# SCH_uCompute_remote_2026-03-16.net
KiCad netlist of a schematic drawn in EasyEDA
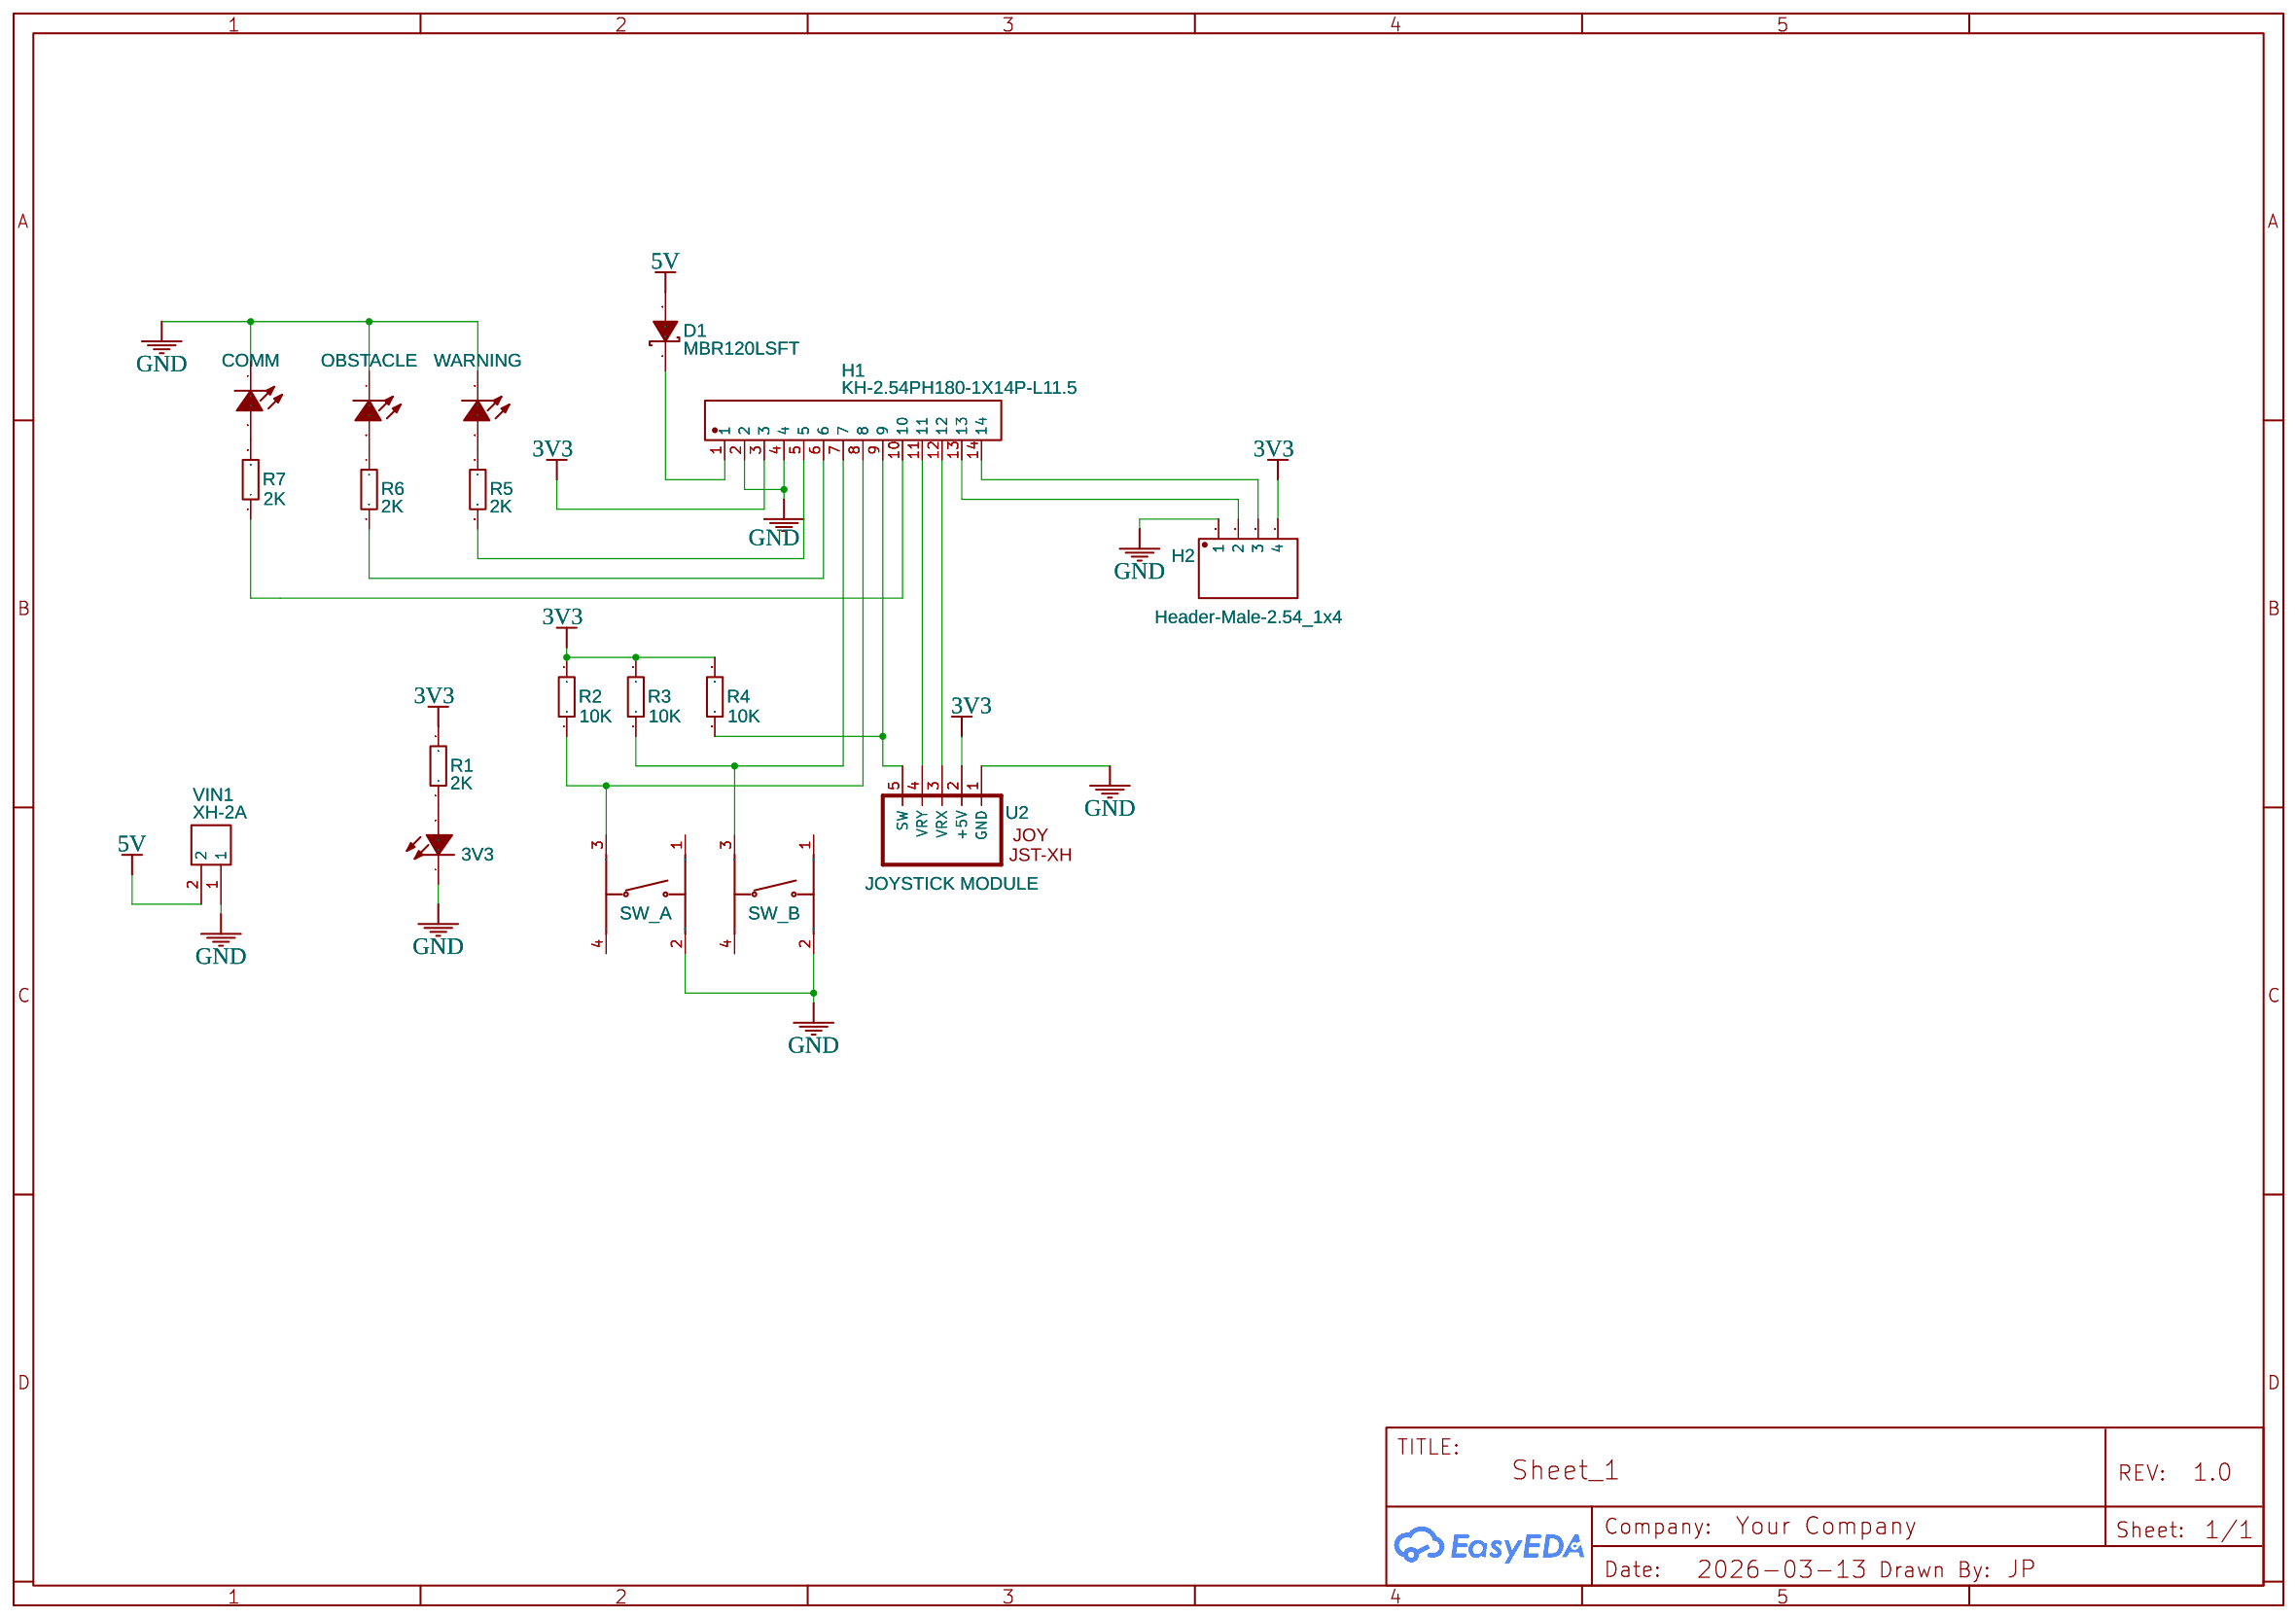
[diagram p0: schematic sheet]

(export (version "E")
  (design (tool "Eeschema 10.0.6"))
  (components
    (comp (ref "3V3")
      (value "XL-1206QPC")
      (fields (field (name "Manufacturer") "LCSC"))
      (libsource (lib "") (part "XL-1206QPC_1"))
    )
    (comp (ref "COMM")
      (value "XL-1206QPC")
      (fields (field (name "Manufacturer") "LCSC"))
      (libsource (lib "") (part "XL-1206QPC"))
    )
    (comp (ref "D1")
      (value "MBR120LSFT")
      (fields
        (field (name "Manufacturer Part") "SS110A")
        (field (name "Manufacturer") "Yangzhou Yangjie Elec Tech")
      )
      (libsource (lib "") (part "SS110A"))
    )
    (comp (ref "H1")
      (value "KH-2.54PH180-1X14P-L11.5")
      (fields (field (name "Manufacturer") "kinghelm(金航标)"))
      (libsource (lib "") (part "KH-2.54PH180-1X14P-L11.5"))
    )
    (comp (ref "H2")
      (value "Header-Male-2.54_1x4")
      (fields (field (name "Manufacturer Part") "B-2100S04P-A110") (field (name "Manufacturer") "Ckmtw(灿科盟)"))
      (libsource (lib "") (part "Header-Male-2.54_1x4"))
    )
    (comp (ref "OBSTACLE")
      (value "XL-1206QPC")
      (fields (field (name "Manufacturer") "LCSC"))
      (libsource (lib "") (part "XL-1206QPC_3"))
    )
    (comp (ref "R1")
      (value "2K")
      (fields (field (name "Manufacturer Part") "RC0805DR-071KL") (field (name "Manufacturer") "YAGEO(国巨)"))
      (libsource (lib "") (part "RC0805DR-071KL"))
    )
    (comp (ref "R2")
      (value "10K")
      (fields (field (name "Manufacturer Part") "RC0805DR-071KL") (field (name "Manufacturer") "YAGEO(国巨)"))
      (libsource (lib "") (part "RC0805DR-071KL"))
    )
    (comp (ref "R3")
      (value "10K")
      (fields (field (name "Manufacturer Part") "RC0805DR-071KL") (field (name "Manufacturer") "YAGEO(国巨)"))
      (libsource (lib "") (part "RC0805DR-071KL"))
    )
    (comp (ref "R4")
      (value "10K")
      (fields (field (name "Manufacturer Part") "RC0805DR-071KL") (field (name "Manufacturer") "YAGEO(国巨)"))
      (libsource (lib "") (part "RC0805DR-071KL"))
    )
    (comp (ref "R5")
      (value "2K")
      (fields (field (name "Manufacturer Part") "RC0805DR-071KL") (field (name "Manufacturer") "YAGEO(国巨)"))
      (libsource (lib "") (part "RC0805DR-071KL_1"))
    )
    (comp (ref "R6")
      (value "2K")
      (fields (field (name "Manufacturer Part") "RC0805DR-071KL") (field (name "Manufacturer") "YAGEO(国巨)"))
      (libsource (lib "") (part "RC0805DR-071KL_1"))
    )
    (comp (ref "R7")
      (value "2K")
      (fields (field (name "Manufacturer Part") "RC0805DR-071KL") (field (name "Manufacturer") "YAGEO(国巨)"))
      (libsource (lib "") (part "RC0805DR-071KL"))
    )
    (comp (ref "SW_A")
      (value "12X12X7.3")
      (fields (field (name "Manufacturer Part") "12x12x7.3 黄头") (field (name "Manufacturer") "BOOMELE(博穆精密)"))
      (libsource (lib "") (part "12X12X7.3"))
    )
    (comp (ref "SW_B")
      (value "12X12X7.3")
      (fields (field (name "Manufacturer Part") "12x12x7.3 黄头") (field (name "Manufacturer") "BOOMELE(博穆精密)"))
      (libsource (lib "") (part "12X12X7.3_1"))
    )
    (comp (ref "U2") (value "JOYSTICK MODULE") (libsource (lib "") (part "JOYSTICK MODULE")))
    (comp (ref "VIN1")
      (value "XH-2A")
      (fields (field (name "Manufacturer") "BOOMELE(博穆精密)"))
      (libsource (lib "") (part "XH-2A"))
    )
    (comp (ref "WARNING")
      (value "XL-1206QPC")
      (fields (field (name "Manufacturer") "LCSC"))
      (libsource (lib "") (part "XL-1206QPC_2"))
    )
  )
  (nets
    (net (code "1") (name "3V3") (class "Default")
      (node (ref "H1") (pin "3") (pinfunction "3_3") (pintype "unspecified"))
      (node (ref "H2") (pin "4") (pinfunction "4_4") (pintype "unspecified"))
      (node (ref "R1") (pin "2") (pinfunction "2_2") (pintype "unspecified"))
      (node (ref "R2") (pin "2") (pinfunction "2_2") (pintype "unspecified"))
      (node (ref "R3") (pin "2") (pinfunction "2_2") (pintype "unspecified"))
      (node (ref "R4") (pin "2") (pinfunction "2_2") (pintype "unspecified"))
      (node (ref "U2") (pin "2") (pinfunction "+5V_2") (pintype "unspecified"))
    )
    (net (code "2") (name "5V") (class "Default")
      (node (ref "D1") (pin "2") (pinfunction "A_2") (pintype "unspecified"))
      (node (ref "VIN1") (pin "2") (pinfunction "2_2") (pintype "unspecified"))
    )
    (net (code "3") (name "GND") (class "Default")
      (node (ref "3V3") (pin "1") (pinfunction "K_1") (pintype "unspecified"))
      (node (ref "COMM") (pin "1") (pinfunction "K_1") (pintype "unspecified"))
      (node (ref "H1") (pin "2") (pinfunction "2_2") (pintype "unspecified"))
      (node (ref "H1") (pin "4") (pinfunction "4_4") (pintype "unspecified"))
      (node (ref "H2") (pin "1") (pinfunction "1_1") (pintype "unspecified"))
      (node (ref "OBSTACLE") (pin "1") (pinfunction "K_1") (pintype "unspecified"))
      (node (ref "SW_A") (pin "2") (pinfunction "2_2") (pintype "unspecified"))
      (node (ref "SW_B") (pin "2") (pinfunction "2_2") (pintype "unspecified"))
      (node (ref "U2") (pin "1") (pinfunction "GND_1") (pintype "unspecified"))
      (node (ref "VIN1") (pin "1") (pinfunction "1_1") (pintype "unspecified"))
      (node (ref "WARNING") (pin "1") (pinfunction "K_1") (pintype "unspecified"))
    )
    (net (code "4") (name "Net-(3V3-A)") (class "Default")
      (node (ref "3V3") (pin "2") (pinfunction "A_2") (pintype "unspecified"))
      (node (ref "R1") (pin "1") (pinfunction "1_1") (pintype "unspecified"))
    )
    (net (code "5") (name "Net-(COMM-A)") (class "Default")
      (node (ref "COMM") (pin "2") (pinfunction "A_2") (pintype "unspecified"))
      (node (ref "R7") (pin "2") (pinfunction "2_2") (pintype "unspecified"))
    )
    (net (code "6") (name "Net-(D1-K)") (class "Default")
      (node (ref "D1") (pin "1") (pinfunction "K_1") (pintype "unspecified"))
      (node (ref "H1") (pin "1") (pinfunction "1_1") (pintype "unspecified"))
    )
    (net (code "7") (name "Net-(H1-Pad5)") (class "Default")
      (node (ref "H1") (pin "5") (pinfunction "5_5") (pintype "unspecified"))
      (node (ref "R5") (pin "2") (pinfunction "2_2") (pintype "unspecified"))
    )
    (net (code "8") (name "Net-(H1-Pad6)") (class "Default")
      (node (ref "H1") (pin "6") (pinfunction "6_6") (pintype "unspecified"))
      (node (ref "R6") (pin "2") (pinfunction "2_2") (pintype "unspecified"))
    )
    (net (code "9") (name "Net-(H1-Pad7)") (class "Default")
      (node (ref "H1") (pin "7") (pinfunction "7_7") (pintype "unspecified"))
      (node (ref "R3") (pin "1") (pinfunction "1_1") (pintype "unspecified"))
      (node (ref "SW_B") (pin "3") (pinfunction "3_3") (pintype "unspecified"))
    )
    (net (code "10") (name "Net-(H1-Pad8)") (class "Default")
      (node (ref "H1") (pin "8") (pinfunction "8_8") (pintype "unspecified"))
      (node (ref "R2") (pin "1") (pinfunction "1_1") (pintype "unspecified"))
      (node (ref "SW_A") (pin "3") (pinfunction "3_3") (pintype "unspecified"))
    )
    (net (code "11") (name "Net-(H1-Pad10)") (class "Default")
      (node (ref "H1") (pin "10") (pinfunction "10_10") (pintype "unspecified"))
      (node (ref "R7") (pin "1") (pinfunction "1_1") (pintype "unspecified"))
    )
    (net (code "12") (name "Net-(H1-Pad13)") (class "Default")
      (node (ref "H1") (pin "13") (pinfunction "13_13") (pintype "unspecified"))
      (node (ref "H2") (pin "2") (pinfunction "2_2") (pintype "unspecified"))
    )
    (net (code "13") (name "Net-(H1-Pad14)") (class "Default")
      (node (ref "H1") (pin "14") (pinfunction "14_14") (pintype "unspecified"))
      (node (ref "H2") (pin "3") (pinfunction "3_3") (pintype "unspecified"))
    )
    (net (code "14") (name "Net-(OBSTACLE-A)") (class "Default")
      (node (ref "OBSTACLE") (pin "2") (pinfunction "A_2") (pintype "unspecified"))
      (node (ref "R6") (pin "1") (pinfunction "1_1") (pintype "unspecified"))
    )
    (net (code "15") (name "Net-(U2-SW)") (class "Default")
      (node (ref "H1") (pin "9") (pinfunction "9_9") (pintype "unspecified"))
      (node (ref "R4") (pin "1") (pinfunction "1_1") (pintype "unspecified"))
      (node (ref "U2") (pin "5") (pinfunction "SW_5") (pintype "unspecified"))
    )
    (net (code "16") (name "Net-(U2-VRX)") (class "Default")
      (node (ref "H1") (pin "12") (pinfunction "12_12") (pintype "unspecified"))
      (node (ref "U2") (pin "3") (pinfunction "VRX_3") (pintype "unspecified"))
    )
    (net (code "17") (name "Net-(U2-VRY)") (class "Default")
      (node (ref "H1") (pin "11") (pinfunction "11_11") (pintype "unspecified"))
      (node (ref "U2") (pin "4") (pinfunction "VRY_4") (pintype "unspecified"))
    )
    (net (code "18") (name "Net-(WARNING-A)") (class "Default")
      (node (ref "R5") (pin "1") (pinfunction "1_1") (pintype "unspecified"))
      (node (ref "WARNING") (pin "2") (pinfunction "A_2") (pintype "unspecified"))
    )
    (net (code "19") (name "unconnected-(SW_A-Pad1)") (class "Default")
      (node (ref "SW_A") (pin "1") (pinfunction "1_1") (pintype "unspecified"))
    )
    (net (code "20") (name "unconnected-(SW_A-Pad4)") (class "Default")
      (node (ref "SW_A") (pin "4") (pinfunction "4_4") (pintype "unspecified"))
    )
    (net (code "21") (name "unconnected-(SW_B-Pad1)") (class "Default")
      (node (ref "SW_B") (pin "1") (pinfunction "1_1") (pintype "unspecified"))
    )
    (net (code "22") (name "unconnected-(SW_B-Pad4)") (class "Default")
      (node (ref "SW_B") (pin "4") (pinfunction "4_4") (pintype "unspecified"))
    )
  )
)
